# Top_Level.net
KiCad netlist of a schematic drawn in Altium Designer
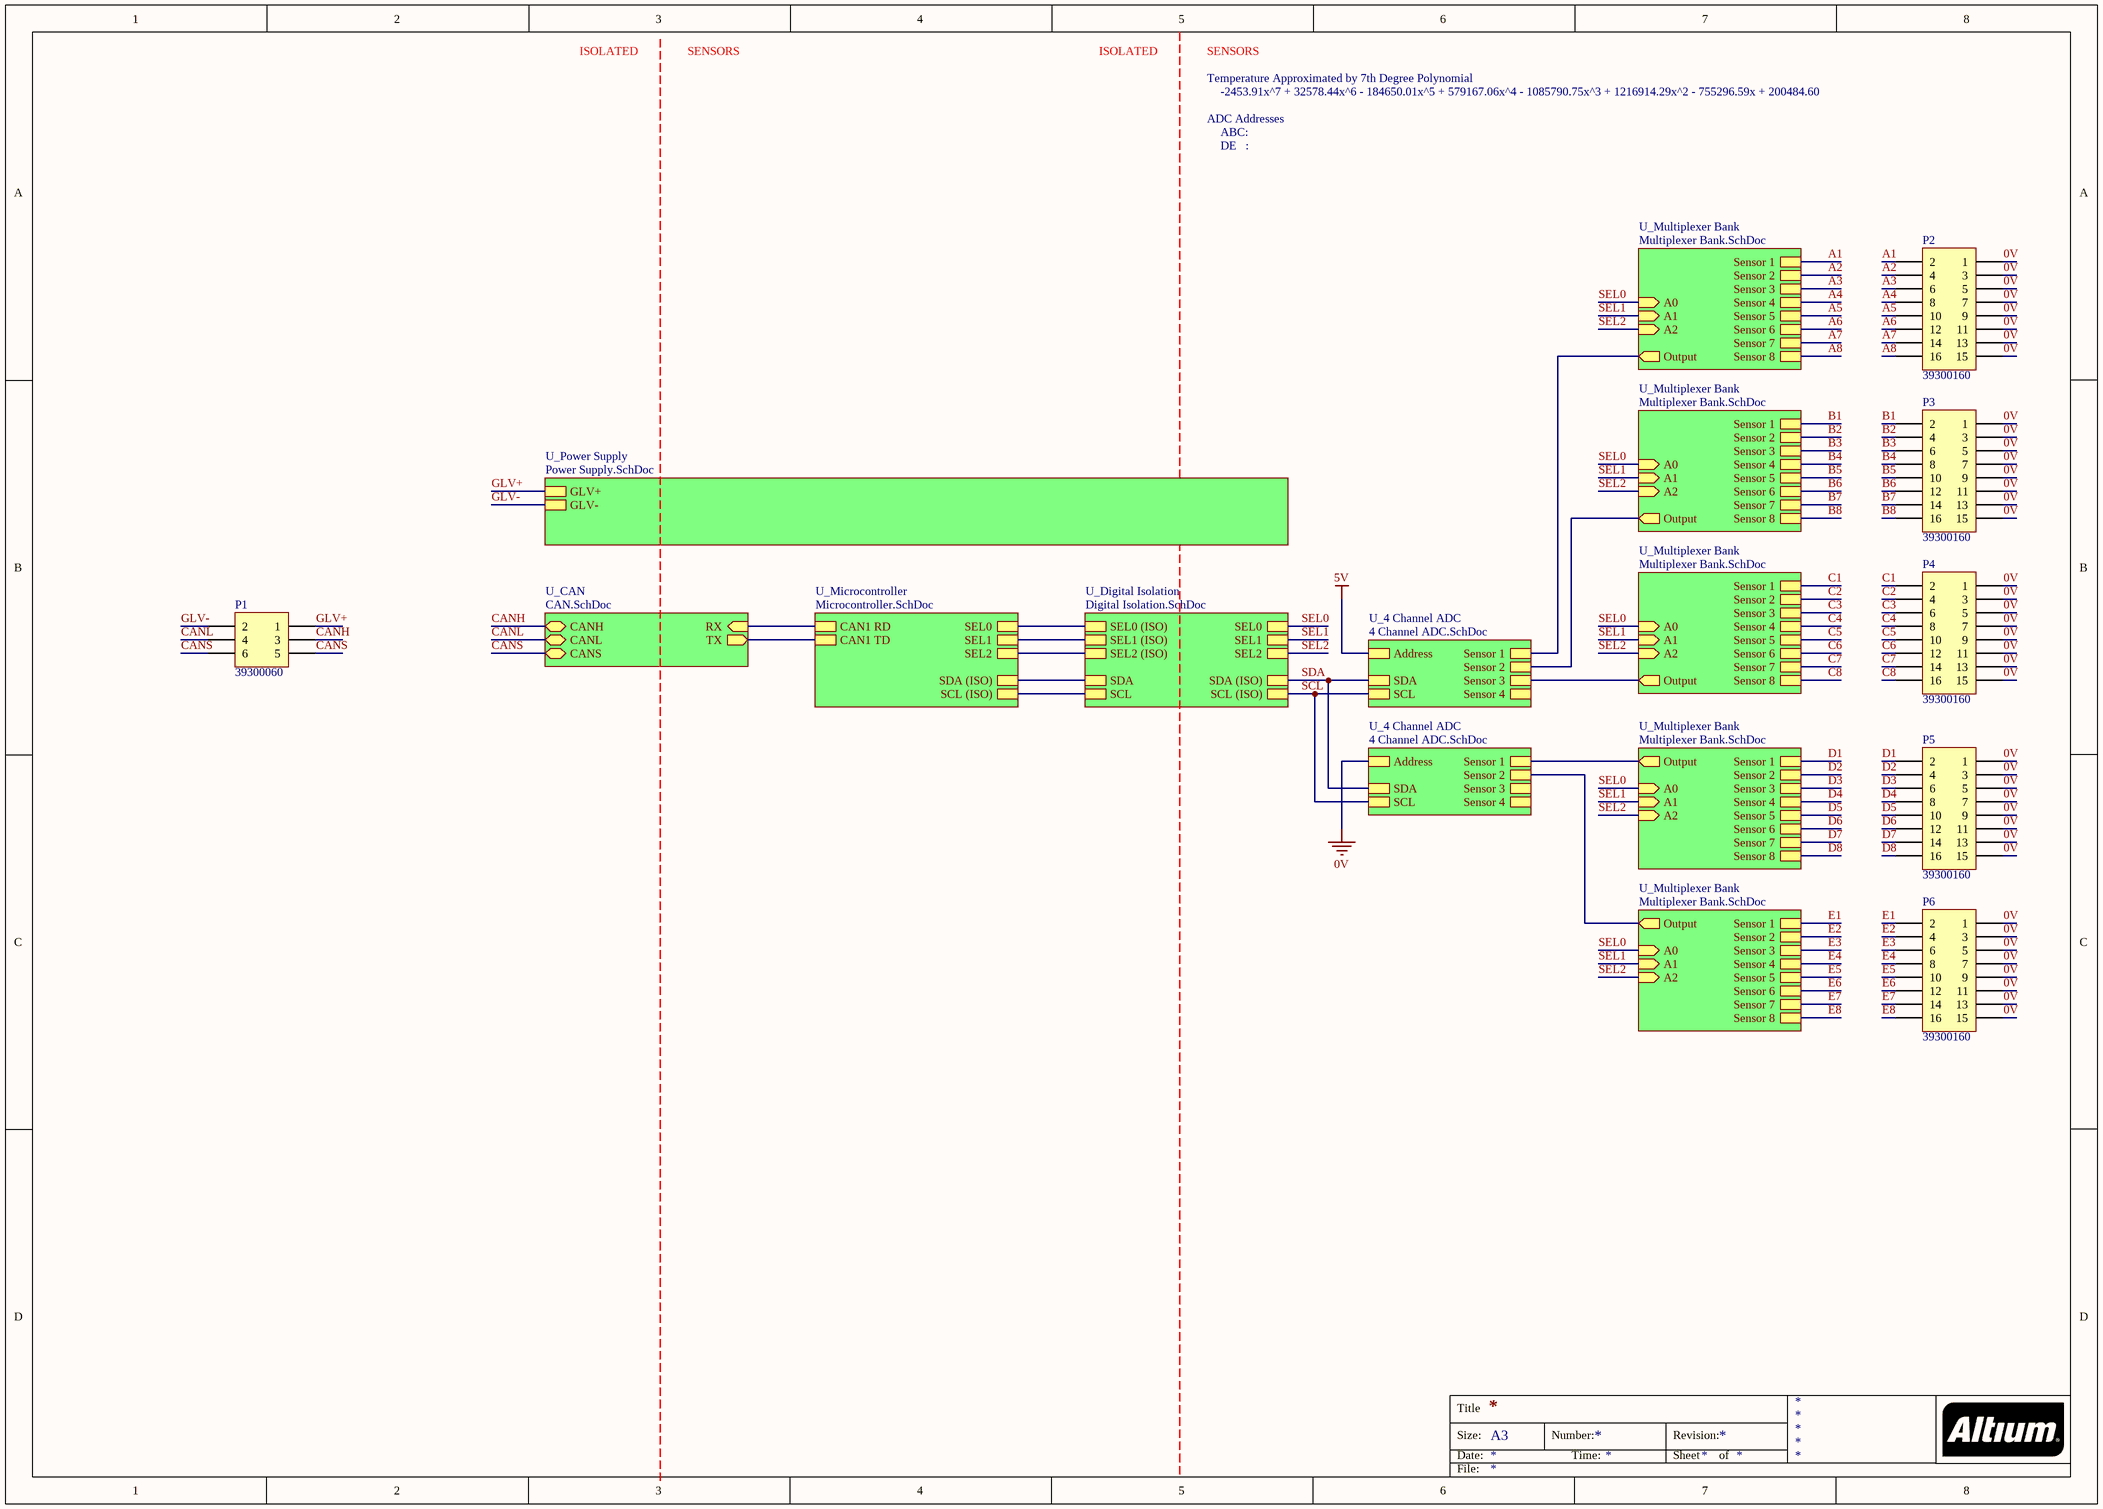
[diagram p0: Top Level.SchDoc]

(export (version "E")
  (design (tool "Eeschema 10.0.6"))
  (components
    (comp (ref "P1")
      (value "39300060")
      (footprint "39300060")
      (fields (field (name "DIGIKEY PART NUMBER") "WM21353-ND") (field (name "CONTACT") "Tin"))
      (libsource (lib "ts_20-standard-connectors") (part "39300060"))
    )
    (comp (ref "P2")
      (value "39300160")
      (footprint "39300160")
      (fields (field (name "DIGIKEY PART NUMBER") "WM21358-ND") (field (name "CONTACT") "Tin"))
      (libsource (lib "ts_20-standard-connectors") (part "39300160"))
    )
    (comp (ref "P3")
      (value "39300160")
      (footprint "39300160")
      (fields (field (name "DIGIKEY PART NUMBER") "WM21358-ND") (field (name "CONTACT") "Tin"))
      (libsource (lib "ts_20-standard-connectors") (part "39300160"))
    )
    (comp (ref "P4")
      (value "39300160")
      (footprint "39300160")
      (fields (field (name "DIGIKEY PART NUMBER") "WM21358-ND") (field (name "CONTACT") "Tin"))
      (libsource (lib "ts_20-standard-connectors") (part "39300160"))
    )
    (comp (ref "P5")
      (value "39300160")
      (footprint "39300160")
      (fields (field (name "DIGIKEY PART NUMBER") "WM21358-ND") (field (name "CONTACT") "Tin"))
      (libsource (lib "ts_20-standard-connectors") (part "39300160"))
    )
    (comp (ref "P6")
      (value "39300160")
      (footprint "39300160")
      (fields (field (name "DIGIKEY PART NUMBER") "WM21358-ND") (field (name "CONTACT") "Tin"))
      (libsource (lib "ts_20-standard-connectors") (part "39300160"))
    )
  )
  (nets
    (net (code "1") (name "/A1") (class "Default")
      (node (ref "P2") (pin "2") (pinfunction "2_2") (pintype "passive"))
    )
    (net (code "2") (name "/A2") (class "Default")
      (node (ref "P2") (pin "4") (pinfunction "4_4") (pintype "passive"))
    )
    (net (code "3") (name "/A3") (class "Default")
      (node (ref "P2") (pin "6") (pinfunction "6_6") (pintype "passive"))
    )
    (net (code "4") (name "/A4") (class "Default")
      (node (ref "P2") (pin "8") (pinfunction "8_8") (pintype "passive"))
    )
    (net (code "5") (name "/A5") (class "Default")
      (node (ref "P2") (pin "10") (pinfunction "10_10") (pintype "passive"))
    )
    (net (code "6") (name "/A6") (class "Default")
      (node (ref "P2") (pin "12") (pinfunction "12_12") (pintype "passive"))
    )
    (net (code "7") (name "/A7") (class "Default")
      (node (ref "P2") (pin "14") (pinfunction "14_14") (pintype "passive"))
    )
    (net (code "8") (name "/A8") (class "Default")
      (node (ref "P2") (pin "16") (pinfunction "16_16") (pintype "passive"))
    )
    (net (code "9") (name "/B1") (class "Default")
      (node (ref "P3") (pin "2") (pinfunction "2_2") (pintype "passive"))
    )
    (net (code "10") (name "/B2") (class "Default")
      (node (ref "P3") (pin "4") (pinfunction "4_4") (pintype "passive"))
    )
    (net (code "11") (name "/B3") (class "Default")
      (node (ref "P3") (pin "6") (pinfunction "6_6") (pintype "passive"))
    )
    (net (code "12") (name "/B4") (class "Default")
      (node (ref "P3") (pin "8") (pinfunction "8_8") (pintype "passive"))
    )
    (net (code "13") (name "/B5") (class "Default")
      (node (ref "P3") (pin "10") (pinfunction "10_10") (pintype "passive"))
    )
    (net (code "14") (name "/B6") (class "Default")
      (node (ref "P3") (pin "12") (pinfunction "12_12") (pintype "passive"))
    )
    (net (code "15") (name "/B7") (class "Default")
      (node (ref "P3") (pin "14") (pinfunction "14_14") (pintype "passive"))
    )
    (net (code "16") (name "/B8") (class "Default")
      (node (ref "P3") (pin "16") (pinfunction "16_16") (pintype "passive"))
    )
    (net (code "17") (name "/C1") (class "Default")
      (node (ref "P4") (pin "2") (pinfunction "2_2") (pintype "passive"))
    )
    (net (code "18") (name "/C2") (class "Default")
      (node (ref "P4") (pin "4") (pinfunction "4_4") (pintype "passive"))
    )
    (net (code "19") (name "/C3") (class "Default")
      (node (ref "P4") (pin "6") (pinfunction "6_6") (pintype "passive"))
    )
    (net (code "20") (name "/C4") (class "Default")
      (node (ref "P4") (pin "8") (pinfunction "8_8") (pintype "passive"))
    )
    (net (code "21") (name "/C5") (class "Default")
      (node (ref "P4") (pin "10") (pinfunction "10_10") (pintype "passive"))
    )
    (net (code "22") (name "/C6") (class "Default")
      (node (ref "P4") (pin "12") (pinfunction "12_12") (pintype "passive"))
    )
    (net (code "23") (name "/C7") (class "Default")
      (node (ref "P4") (pin "14") (pinfunction "14_14") (pintype "passive"))
    )
    (net (code "24") (name "/C8") (class "Default")
      (node (ref "P4") (pin "16") (pinfunction "16_16") (pintype "passive"))
    )
    (net (code "26") (name "/CANH") (class "Default")
      (node (ref "P1") (pin "3") (pinfunction "3_3") (pintype "passive"))
    )
    (net (code "27") (name "/CANL") (class "Default")
      (node (ref "P1") (pin "4") (pinfunction "4_4") (pintype "passive"))
    )
    (net (code "28") (name "/CANS") (class "Default")
      (node (ref "P1") (pin "5") (pinfunction "5_5") (pintype "passive"))
      (node (ref "P1") (pin "6") (pinfunction "6_6") (pintype "passive"))
    )
    (net (code "29") (name "/D1") (class "Default")
      (node (ref "P5") (pin "2") (pinfunction "2_2") (pintype "passive"))
    )
    (net (code "30") (name "/D2") (class "Default")
      (node (ref "P5") (pin "4") (pinfunction "4_4") (pintype "passive"))
    )
    (net (code "31") (name "/D3") (class "Default")
      (node (ref "P5") (pin "6") (pinfunction "6_6") (pintype "passive"))
    )
    (net (code "32") (name "/D4") (class "Default")
      (node (ref "P5") (pin "8") (pinfunction "8_8") (pintype "passive"))
    )
    (net (code "33") (name "/D5") (class "Default")
      (node (ref "P5") (pin "10") (pinfunction "10_10") (pintype "passive"))
    )
    (net (code "34") (name "/D6") (class "Default")
      (node (ref "P5") (pin "12") (pinfunction "12_12") (pintype "passive"))
    )
    (net (code "35") (name "/D7") (class "Default")
      (node (ref "P5") (pin "14") (pinfunction "14_14") (pintype "passive"))
    )
    (net (code "36") (name "/D8") (class "Default")
      (node (ref "P5") (pin "16") (pinfunction "16_16") (pintype "passive"))
    )
    (net (code "37") (name "/E1") (class "Default")
      (node (ref "P6") (pin "2") (pinfunction "2_2") (pintype "passive"))
    )
    (net (code "38") (name "/E2") (class "Default")
      (node (ref "P6") (pin "4") (pinfunction "4_4") (pintype "passive"))
    )
    (net (code "39") (name "/E3") (class "Default")
      (node (ref "P6") (pin "6") (pinfunction "6_6") (pintype "passive"))
    )
    (net (code "40") (name "/E4") (class "Default")
      (node (ref "P6") (pin "8") (pinfunction "8_8") (pintype "passive"))
    )
    (net (code "41") (name "/E5") (class "Default")
      (node (ref "P6") (pin "10") (pinfunction "10_10") (pintype "passive"))
    )
    (net (code "42") (name "/E6") (class "Default")
      (node (ref "P6") (pin "12") (pinfunction "12_12") (pintype "passive"))
    )
    (net (code "43") (name "/E7") (class "Default")
      (node (ref "P6") (pin "14") (pinfunction "14_14") (pintype "passive"))
    )
    (net (code "44") (name "/E8") (class "Default")
      (node (ref "P6") (pin "16") (pinfunction "16_16") (pintype "passive"))
    )
    (net (code "45") (name "/GLV+") (class "Default")
      (node (ref "P1") (pin "1") (pinfunction "1_1") (pintype "passive"))
    )
    (net (code "46") (name "/GLV-") (class "Default")
      (node (ref "P1") (pin "2") (pinfunction "2_2") (pintype "passive"))
    )
    (net (code "66") (name "0V") (class "Default")
      (node (ref "P2") (pin "1") (pinfunction "1_1") (pintype "passive"))
      (node (ref "P2") (pin "11") (pinfunction "11_11") (pintype "passive"))
      (node (ref "P2") (pin "13") (pinfunction "13_13") (pintype "passive"))
      (node (ref "P2") (pin "15") (pinfunction "15_15") (pintype "passive"))
      (node (ref "P2") (pin "3") (pinfunction "3_3") (pintype "passive"))
      (node (ref "P2") (pin "5") (pinfunction "5_5") (pintype "passive"))
      (node (ref "P2") (pin "7") (pinfunction "7_7") (pintype "passive"))
      (node (ref "P2") (pin "9") (pinfunction "9_9") (pintype "passive"))
      (node (ref "P3") (pin "1") (pinfunction "1_1") (pintype "passive"))
      (node (ref "P3") (pin "11") (pinfunction "11_11") (pintype "passive"))
      (node (ref "P3") (pin "13") (pinfunction "13_13") (pintype "passive"))
      (node (ref "P3") (pin "15") (pinfunction "15_15") (pintype "passive"))
      (node (ref "P3") (pin "3") (pinfunction "3_3") (pintype "passive"))
      (node (ref "P3") (pin "5") (pinfunction "5_5") (pintype "passive"))
      (node (ref "P3") (pin "7") (pinfunction "7_7") (pintype "passive"))
      (node (ref "P3") (pin "9") (pinfunction "9_9") (pintype "passive"))
      (node (ref "P4") (pin "1") (pinfunction "1_1") (pintype "passive"))
      (node (ref "P4") (pin "11") (pinfunction "11_11") (pintype "passive"))
      (node (ref "P4") (pin "13") (pinfunction "13_13") (pintype "passive"))
      (node (ref "P4") (pin "15") (pinfunction "15_15") (pintype "passive"))
      (node (ref "P4") (pin "3") (pinfunction "3_3") (pintype "passive"))
      (node (ref "P4") (pin "5") (pinfunction "5_5") (pintype "passive"))
      (node (ref "P4") (pin "7") (pinfunction "7_7") (pintype "passive"))
      (node (ref "P4") (pin "9") (pinfunction "9_9") (pintype "passive"))
      (node (ref "P5") (pin "1") (pinfunction "1_1") (pintype "passive"))
      (node (ref "P5") (pin "11") (pinfunction "11_11") (pintype "passive"))
      (node (ref "P5") (pin "13") (pinfunction "13_13") (pintype "passive"))
      (node (ref "P5") (pin "15") (pinfunction "15_15") (pintype "passive"))
      (node (ref "P5") (pin "3") (pinfunction "3_3") (pintype "passive"))
      (node (ref "P5") (pin "5") (pinfunction "5_5") (pintype "passive"))
      (node (ref "P5") (pin "7") (pinfunction "7_7") (pintype "passive"))
      (node (ref "P5") (pin "9") (pinfunction "9_9") (pintype "passive"))
      (node (ref "P6") (pin "1") (pinfunction "1_1") (pintype "passive"))
      (node (ref "P6") (pin "11") (pinfunction "11_11") (pintype "passive"))
      (node (ref "P6") (pin "13") (pinfunction "13_13") (pintype "passive"))
      (node (ref "P6") (pin "15") (pinfunction "15_15") (pintype "passive"))
      (node (ref "P6") (pin "3") (pinfunction "3_3") (pintype "passive"))
      (node (ref "P6") (pin "5") (pinfunction "5_5") (pintype "passive"))
      (node (ref "P6") (pin "7") (pinfunction "7_7") (pintype "passive"))
      (node (ref "P6") (pin "9") (pinfunction "9_9") (pintype "passive"))
    )
  )
)
